# pcb__2024-09-09.net
KiCad netlist of a schematic drawn in EasyEDA Pro
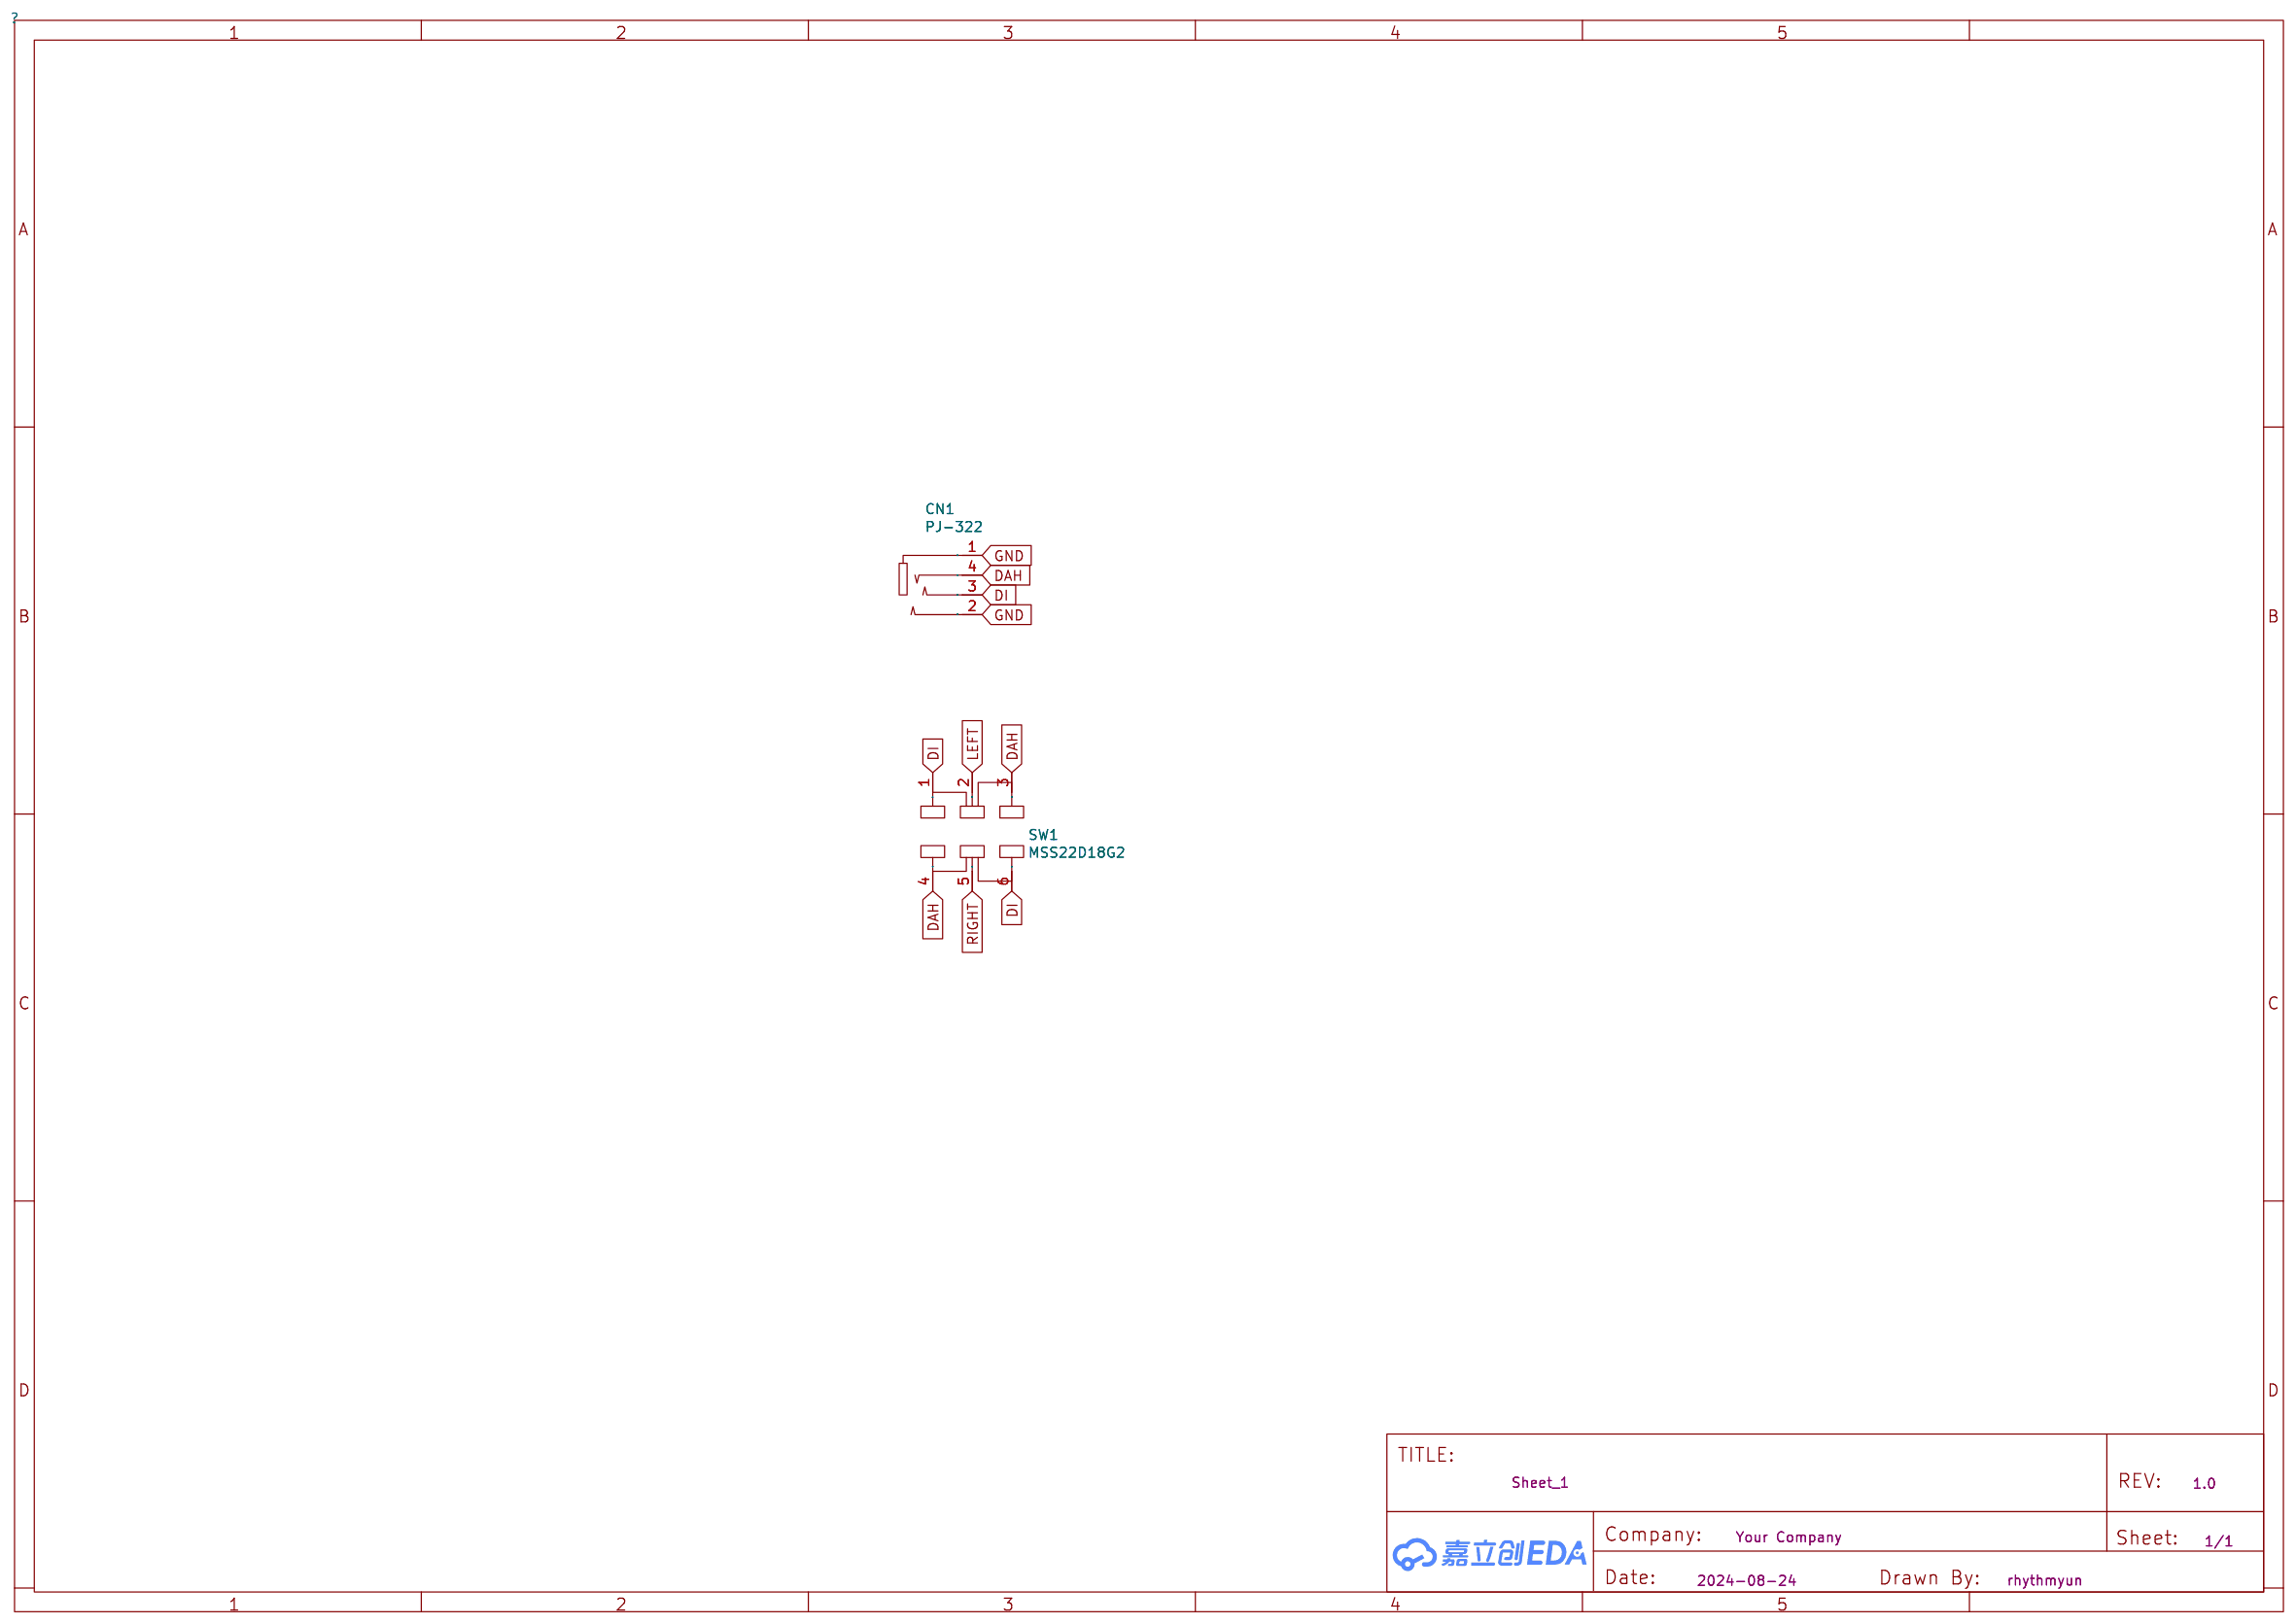
[diagram p0: schematic sheet]

(export (version "E")
  (design (tool "Eeschema 10.0.6"))
  (components
    (comp (ref "CN1")
      (value "PJ-322")
      (footprint "easyedapro:AUDIO-TH_HOOYA_PJ-322")
      (fields (field (name "Manufacturer Part") "PJ-322环保") (field (name "Manufacturer") "HOOYA(皓宇电子)"))
      (libsource (lib "easyedapro") (part "PJ-322"))
    )
    (comp (ref "SW1")
      (value "MSS22D18G2")
      (footprint "easyedapro:SW-TH_MSS22D18GX")
      (fields (field (name "Manufacturer") "SHOU HAN(首韩)"))
      (libsource (lib "easyedapro") (part "MSS22D18G2"))
    )
  )
  (nets
    (net (code "1") (name "DAH") (class "Default")
      (node (ref "CN1") (pin "4") (pinfunction "4_4") (pintype "unspecified"))
      (node (ref "SW1") (pin "3") (pinfunction "3_3") (pintype "unspecified"))
      (node (ref "SW1") (pin "4") (pinfunction "4_4") (pintype "unspecified"))
    )
    (net (code "2") (name "DI") (class "Default")
      (node (ref "CN1") (pin "3") (pinfunction "3_3") (pintype "unspecified"))
      (node (ref "SW1") (pin "1") (pinfunction "1_1") (pintype "unspecified"))
      (node (ref "SW1") (pin "6") (pinfunction "6_6") (pintype "unspecified"))
    )
    (net (code "3") (name "GND") (class "Default")
      (node (ref "CN1") (pin "1") (pinfunction "1_1") (pintype "unspecified"))
      (node (ref "CN1") (pin "2") (pinfunction "2_2") (pintype "unspecified"))
    )
    (net (code "4") (name "LEFT") (class "Default")
      (node (ref "SW1") (pin "2") (pinfunction "2_2") (pintype "unspecified"))
    )
    (net (code "5") (name "RIGHT") (class "Default")
      (node (ref "SW1") (pin "5") (pinfunction "5_5") (pintype "unspecified"))
    )
  )
)
